# Boost_Converter.net
KiCad netlist of a schematic drawn in Altium Designer
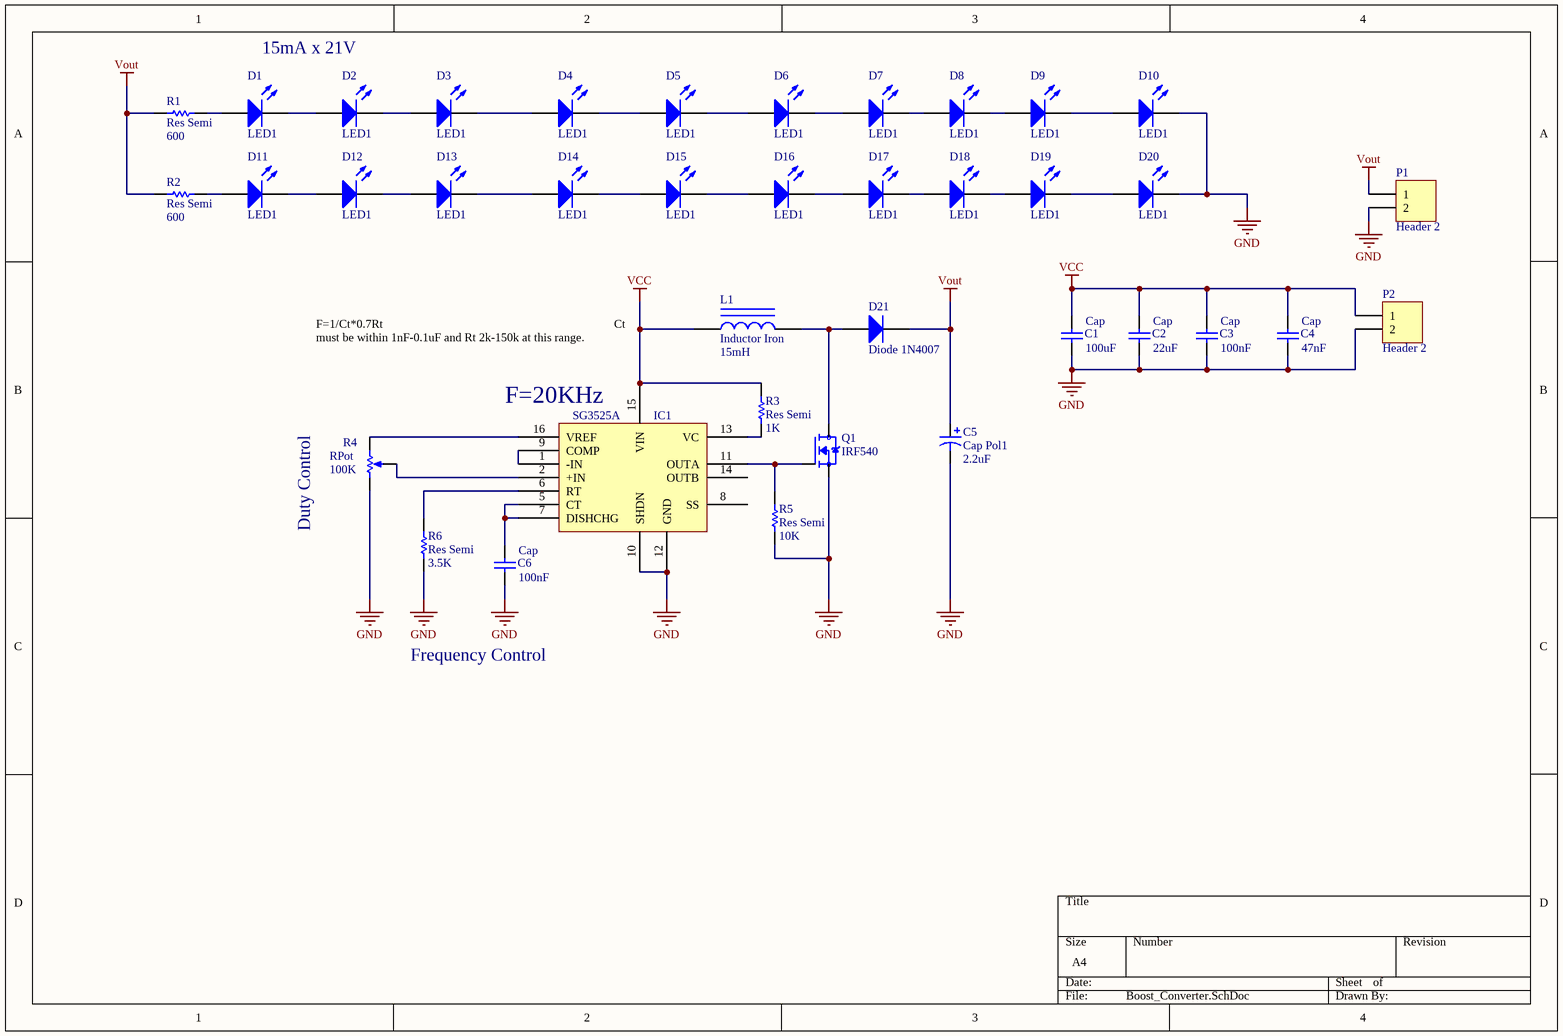
[diagram p0: Boost_Converter.SchDoc]

(export (version "E")
  (design (tool "Eeschema 10.0.6"))
  (components
    (comp (ref "C1")
      (value "Cap")
      (footprint "RAD-0.3")
      (description "Capacitor")
      (fields (field (name "ALTIUM_VALUE") "100uF") (field (name "PUBLISHER") "Altium Limited"))
      (libsource (lib "Miscellaneous Devices") (part "Cap"))
    )
    (comp (ref "C2")
      (value "Cap")
      (footprint "RAD-0.3")
      (description "Capacitor")
      (fields (field (name "ALTIUM_VALUE") "22uF") (field (name "PUBLISHER") "Altium Limited"))
      (libsource (lib "Miscellaneous Devices") (part "Cap"))
    )
    (comp (ref "C3")
      (value "Cap")
      (footprint "RAD-0.3")
      (description "Capacitor")
      (fields (field (name "ALTIUM_VALUE") "100nF") (field (name "PUBLISHER") "Altium Limited"))
      (libsource (lib "Miscellaneous Devices") (part "Cap"))
    )
    (comp (ref "C4")
      (value "Cap")
      (footprint "RAD-0.3")
      (description "Capacitor")
      (fields (field (name "ALTIUM_VALUE") "47nF") (field (name "PUBLISHER") "Altium Limited"))
      (libsource (lib "Miscellaneous Devices") (part "Cap"))
    )
    (comp (ref "C5")
      (value "Cap Pol1")
      (footprint "RB7.6-15")
      (description "Polarized Capacitor (Radial)")
      (fields (field (name "ALTIUM_VALUE") "2.2uF") (field (name "PUBLISHER") "Altium Limited"))
      (libsource (lib "Miscellaneous Devices") (part "Cap Pol1"))
    )
    (comp (ref "C6")
      (value "Cap")
      (footprint "RAD-0.3")
      (description "Capacitor")
      (fields (field (name "ALTIUM_VALUE") "100nF") (field (name "PUBLISHER") "Altium Limited"))
      (libsource (lib "Miscellaneous Devices") (part "Cap"))
    )
    (comp (ref "D1")
      (value "LED1")
      (footprint "LED-1")
      (description "Typical RED GaAs LED")
      (fields (field (name "PUBLISHER") "Altium Limited"))
      (libsource (lib "Miscellaneous Devices") (part "LED1"))
    )
    (comp (ref "D2")
      (value "LED1")
      (footprint "LED-1")
      (description "Typical RED GaAs LED")
      (fields (field (name "PUBLISHER") "Altium Limited"))
      (libsource (lib "Miscellaneous Devices") (part "LED1"))
    )
    (comp (ref "D3")
      (value "LED1")
      (footprint "LED-1")
      (description "Typical RED GaAs LED")
      (fields (field (name "PUBLISHER") "Altium Limited"))
      (libsource (lib "Miscellaneous Devices") (part "LED1"))
    )
    (comp (ref "D4")
      (value "LED1")
      (footprint "LED-1")
      (description "Typical RED GaAs LED")
      (fields (field (name "PUBLISHER") "Altium Limited"))
      (libsource (lib "Miscellaneous Devices") (part "LED1"))
    )
    (comp (ref "D5")
      (value "LED1")
      (footprint "LED-1")
      (description "Typical RED GaAs LED")
      (fields (field (name "PUBLISHER") "Altium Limited"))
      (libsource (lib "Miscellaneous Devices") (part "LED1"))
    )
    (comp (ref "D6")
      (value "LED1")
      (footprint "LED-1")
      (description "Typical RED GaAs LED")
      (fields (field (name "PUBLISHER") "Altium Limited"))
      (libsource (lib "Miscellaneous Devices") (part "LED1"))
    )
    (comp (ref "D7")
      (value "LED1")
      (footprint "LED-1")
      (description "Typical RED GaAs LED")
      (fields (field (name "PUBLISHER") "Altium Limited"))
      (libsource (lib "Miscellaneous Devices") (part "LED1"))
    )
    (comp (ref "D8")
      (value "LED1")
      (footprint "LED-1")
      (description "Typical RED GaAs LED")
      (fields (field (name "PUBLISHER") "Altium Limited"))
      (libsource (lib "Miscellaneous Devices") (part "LED1"))
    )
    (comp (ref "D9")
      (value "LED1")
      (footprint "LED-1")
      (description "Typical RED GaAs LED")
      (fields (field (name "PUBLISHER") "Altium Limited"))
      (libsource (lib "Miscellaneous Devices") (part "LED1"))
    )
    (comp (ref "D10")
      (value "LED1")
      (footprint "LED-1")
      (description "Typical RED GaAs LED")
      (fields (field (name "PUBLISHER") "Altium Limited"))
      (libsource (lib "Miscellaneous Devices") (part "LED1"))
    )
    (comp (ref "D11")
      (value "LED1")
      (footprint "LED-1")
      (description "Typical RED GaAs LED")
      (fields (field (name "PUBLISHER") "Altium Limited"))
      (libsource (lib "Miscellaneous Devices") (part "LED1"))
    )
    (comp (ref "D12")
      (value "LED1")
      (footprint "LED-1")
      (description "Typical RED GaAs LED")
      (fields (field (name "PUBLISHER") "Altium Limited"))
      (libsource (lib "Miscellaneous Devices") (part "LED1"))
    )
    (comp (ref "D13")
      (value "LED1")
      (footprint "LED-1")
      (description "Typical RED GaAs LED")
      (fields (field (name "PUBLISHER") "Altium Limited"))
      (libsource (lib "Miscellaneous Devices") (part "LED1"))
    )
    (comp (ref "D14")
      (value "LED1")
      (footprint "LED-1")
      (description "Typical RED GaAs LED")
      (fields (field (name "PUBLISHER") "Altium Limited"))
      (libsource (lib "Miscellaneous Devices") (part "LED1"))
    )
    (comp (ref "D15")
      (value "LED1")
      (footprint "LED-1")
      (description "Typical RED GaAs LED")
      (fields (field (name "PUBLISHER") "Altium Limited"))
      (libsource (lib "Miscellaneous Devices") (part "LED1"))
    )
    (comp (ref "D16")
      (value "LED1")
      (footprint "LED-1")
      (description "Typical RED GaAs LED")
      (fields (field (name "PUBLISHER") "Altium Limited"))
      (libsource (lib "Miscellaneous Devices") (part "LED1"))
    )
    (comp (ref "D17")
      (value "LED1")
      (footprint "LED-1")
      (description "Typical RED GaAs LED")
      (fields (field (name "PUBLISHER") "Altium Limited"))
      (libsource (lib "Miscellaneous Devices") (part "LED1"))
    )
    (comp (ref "D18")
      (value "LED1")
      (footprint "LED-1")
      (description "Typical RED GaAs LED")
      (fields (field (name "PUBLISHER") "Altium Limited"))
      (libsource (lib "Miscellaneous Devices") (part "LED1"))
    )
    (comp (ref "D19")
      (value "LED1")
      (footprint "LED-1")
      (description "Typical RED GaAs LED")
      (fields (field (name "PUBLISHER") "Altium Limited"))
      (libsource (lib "Miscellaneous Devices") (part "LED1"))
    )
    (comp (ref "D20")
      (value "LED1")
      (footprint "LED-1")
      (description "Typical RED GaAs LED")
      (fields (field (name "PUBLISHER") "Altium Limited"))
      (libsource (lib "Miscellaneous Devices") (part "LED1"))
    )
    (comp (ref "D21")
      (value "Diode 1N4007")
      (footprint "DO-41")
      (description "1 Amp General Purpose Rectifier")
      (fields (field (name "PUBLISHER") "Altium Limited"))
      (libsource (lib "Miscellaneous Devices") (part "Diode 1N4007"))
    )
    (comp (ref "IC1")
      (value "SG3525A")
      (footprint "SG3525A")
      (description "PWM GENERATOR IC")
      (libsource (lib "Boost_Shematic_Lib") (part "SG3525A"))
    )
    (comp (ref "L1")
      (value "Inductor Iron")
      (footprint "AXIAL-0.9")
      (description "Magnetic-Core Inductor")
      (fields (field (name "ALTIUM_VALUE") "15mH") (field (name "PUBLISHER") "Altium Limited"))
      (libsource (lib "Miscellaneous Devices") (part "Inductor Iron"))
    )
    (comp (ref "P1")
      (value "Header 2")
      (footprint "HDR1X2")
      (description "Header, 2-Pin")
      (fields (field (name "PUBLISHER") "Altium Limited"))
      (libsource (lib "Miscellaneous Connectors") (part "Header 2"))
    )
    (comp (ref "P2")
      (value "Header 2")
      (footprint "HDR1X2")
      (description "Header, 2-Pin")
      (fields (field (name "PUBLISHER") "Altium Limited"))
      (libsource (lib "Miscellaneous Connectors") (part "Header 2"))
    )
    (comp (ref "Q1")
      (value "IRF540")
      (footprint "TO254P1052X465X1989-3")
      (description "N-Channel 100V 22A _Tc_ 85W _Tc_ Through Hole TO-220AB")
      (fields (field (name "MF") "Vishay"))
      (libsource (lib "IRF540_mosfet") (part "IRF540"))
    )
    (comp (ref "R1")
      (value "Res Semi")
      (footprint "AXIAL-0.5")
      (description "Semiconductor Resistor")
      (fields (field (name "ALTIUM_VALUE") "600") (field (name "PUBLISHER") "Altium Limited"))
      (libsource (lib "Miscellaneous Devices") (part "Res Semi"))
    )
    (comp (ref "R2")
      (value "Res Semi")
      (footprint "AXIAL-0.5")
      (description "Semiconductor Resistor")
      (fields (field (name "ALTIUM_VALUE") "600") (field (name "PUBLISHER") "Altium Limited"))
      (libsource (lib "Miscellaneous Devices") (part "Res Semi"))
    )
    (comp (ref "R3")
      (value "Res Semi")
      (footprint "AXIAL-0.5")
      (description "Semiconductor Resistor")
      (fields (field (name "ALTIUM_VALUE") "1K") (field (name "PUBLISHER") "Altium Limited"))
      (libsource (lib "Miscellaneous Devices") (part "Res Semi"))
    )
    (comp (ref "R4")
      (value "RPot")
      (footprint "VR5")
      (description "Potentiometer")
      (fields (field (name "ALTIUM_VALUE") "100K") (field (name "PUBLISHER") "Altium Limited"))
      (libsource (lib "Miscellaneous Devices") (part "RPot"))
    )
    (comp (ref "R5")
      (value "Res Semi")
      (footprint "AXIAL-0.5")
      (description "Semiconductor Resistor")
      (fields (field (name "ALTIUM_VALUE") "10K") (field (name "PUBLISHER") "Altium Limited"))
      (libsource (lib "Miscellaneous Devices") (part "Res Semi"))
    )
    (comp (ref "R6")
      (value "Res Semi")
      (footprint "AXIAL-0.5")
      (description "Semiconductor Resistor")
      (fields (field (name "ALTIUM_VALUE") "3.5K") (field (name "PUBLISHER") "Altium Limited"))
      (libsource (lib "Miscellaneous Devices") (part "Res Semi"))
    )
  )
  (nets
    (net (code "1") (name "GND") (class "Default")
      (node (ref "C1") (pin "1") (pinfunction "1_1") (pintype "passive"))
      (node (ref "C2") (pin "1") (pinfunction "1_1") (pintype "passive"))
      (node (ref "C3") (pin "1") (pinfunction "1_1") (pintype "passive"))
      (node (ref "C4") (pin "1") (pinfunction "1_1") (pintype "passive"))
      (node (ref "C5") (pin "2") (pinfunction "2_2") (pintype "passive"))
      (node (ref "C6") (pin "1") (pinfunction "1_1") (pintype "passive"))
      (node (ref "D10") (pin "2") (pinfunction "K_2") (pintype "passive"))
      (node (ref "D20") (pin "2") (pinfunction "K_2") (pintype "passive"))
      (node (ref "IC1") (pin "10") (pinfunction "SHDN_10") (pintype "passive"))
      (node (ref "IC1") (pin "12") (pinfunction "GND_12") (pintype "passive"))
      (node (ref "P1") (pin "2") (pinfunction "2_2") (pintype "passive"))
      (node (ref "P2") (pin "2") (pinfunction "2_2") (pintype "passive"))
      (node (ref "Q1") (pin "3") (pinfunction "S_3") (pintype "passive"))
      (node (ref "R4") (pin "1") (pinfunction "TOP_1") (pintype "passive"))
      (node (ref "R5") (pin "1") (pinfunction "1_1") (pintype "passive"))
      (node (ref "R6") (pin "1") (pinfunction "1_1") (pintype "passive"))
    )
    (net (code "2") (name "Net-(D1-A)") (class "Default")
      (node (ref "D1") (pin "1") (pinfunction "A_1") (pintype "passive"))
      (node (ref "R1") (pin "1") (pinfunction "1_1") (pintype "passive"))
    )
    (net (code "3") (name "Net-(D1-K)") (class "Default")
      (node (ref "D1") (pin "2") (pinfunction "K_2") (pintype "passive"))
      (node (ref "D2") (pin "1") (pinfunction "A_1") (pintype "passive"))
    )
    (net (code "4") (name "Net-(D2-K)") (class "Default")
      (node (ref "D2") (pin "2") (pinfunction "K_2") (pintype "passive"))
      (node (ref "D3") (pin "1") (pinfunction "A_1") (pintype "passive"))
    )
    (net (code "5") (name "Net-(D3-K)") (class "Default")
      (node (ref "D3") (pin "2") (pinfunction "K_2") (pintype "passive"))
      (node (ref "D4") (pin "1") (pinfunction "A_1") (pintype "passive"))
    )
    (net (code "6") (name "Net-(D4-K)") (class "Default")
      (node (ref "D4") (pin "2") (pinfunction "K_2") (pintype "passive"))
      (node (ref "D5") (pin "1") (pinfunction "A_1") (pintype "passive"))
    )
    (net (code "7") (name "Net-(D5-K)") (class "Default")
      (node (ref "D5") (pin "2") (pinfunction "K_2") (pintype "passive"))
      (node (ref "D6") (pin "1") (pinfunction "A_1") (pintype "passive"))
    )
    (net (code "8") (name "Net-(D6-K)") (class "Default")
      (node (ref "D6") (pin "2") (pinfunction "K_2") (pintype "passive"))
      (node (ref "D7") (pin "1") (pinfunction "A_1") (pintype "passive"))
    )
    (net (code "9") (name "Net-(D7-K)") (class "Default")
      (node (ref "D7") (pin "2") (pinfunction "K_2") (pintype "passive"))
      (node (ref "D8") (pin "1") (pinfunction "A_1") (pintype "passive"))
    )
    (net (code "10") (name "Net-(D8-K)") (class "Default")
      (node (ref "D8") (pin "2") (pinfunction "K_2") (pintype "passive"))
      (node (ref "D9") (pin "1") (pinfunction "A_1") (pintype "passive"))
    )
    (net (code "11") (name "Net-(D10-A)") (class "Default")
      (node (ref "D10") (pin "1") (pinfunction "A_1") (pintype "passive"))
      (node (ref "D9") (pin "2") (pinfunction "K_2") (pintype "passive"))
    )
    (net (code "12") (name "Net-(D11-A)") (class "Default")
      (node (ref "D11") (pin "1") (pinfunction "A_1") (pintype "passive"))
      (node (ref "R2") (pin "1") (pinfunction "1_1") (pintype "passive"))
    )
    (net (code "13") (name "Net-(D11-K)") (class "Default")
      (node (ref "D11") (pin "2") (pinfunction "K_2") (pintype "passive"))
      (node (ref "D12") (pin "1") (pinfunction "A_1") (pintype "passive"))
    )
    (net (code "14") (name "Net-(D12-K)") (class "Default")
      (node (ref "D12") (pin "2") (pinfunction "K_2") (pintype "passive"))
      (node (ref "D13") (pin "1") (pinfunction "A_1") (pintype "passive"))
    )
    (net (code "15") (name "Net-(D13-K)") (class "Default")
      (node (ref "D13") (pin "2") (pinfunction "K_2") (pintype "passive"))
      (node (ref "D14") (pin "1") (pinfunction "A_1") (pintype "passive"))
    )
    (net (code "16") (name "Net-(D14-K)") (class "Default")
      (node (ref "D14") (pin "2") (pinfunction "K_2") (pintype "passive"))
      (node (ref "D15") (pin "1") (pinfunction "A_1") (pintype "passive"))
    )
    (net (code "17") (name "Net-(D15-K)") (class "Default")
      (node (ref "D15") (pin "2") (pinfunction "K_2") (pintype "passive"))
      (node (ref "D16") (pin "1") (pinfunction "A_1") (pintype "passive"))
    )
    (net (code "18") (name "Net-(D16-K)") (class "Default")
      (node (ref "D16") (pin "2") (pinfunction "K_2") (pintype "passive"))
      (node (ref "D17") (pin "1") (pinfunction "A_1") (pintype "passive"))
    )
    (net (code "19") (name "Net-(D17-K)") (class "Default")
      (node (ref "D17") (pin "2") (pinfunction "K_2") (pintype "passive"))
      (node (ref "D18") (pin "1") (pinfunction "A_1") (pintype "passive"))
    )
    (net (code "20") (name "Net-(D18-K)") (class "Default")
      (node (ref "D18") (pin "2") (pinfunction "K_2") (pintype "passive"))
      (node (ref "D19") (pin "1") (pinfunction "A_1") (pintype "passive"))
    )
    (net (code "21") (name "Net-(D19-K)") (class "Default")
      (node (ref "D19") (pin "2") (pinfunction "K_2") (pintype "passive"))
      (node (ref "D20") (pin "1") (pinfunction "A_1") (pintype "passive"))
    )
    (net (code "22") (name "Net-(D21-A)") (class "Default")
      (node (ref "D21") (pin "1") (pinfunction "A_1") (pintype "passive"))
      (node (ref "L1") (pin "2") (pinfunction "2_2") (pintype "passive"))
      (node (ref "Q1") (pin "2") (pinfunction "D_2") (pintype "passive"))
    )
    (net (code "23") (name "Net-(IC1-+IN)") (class "Default")
      (node (ref "IC1") (pin "2") (pinfunction "+IN_2") (pintype "passive"))
      (node (ref "R4") (pin "3") (pinfunction "TAP_3") (pintype "passive"))
    )
    (net (code "24") (name "Net-(IC1--IN)") (class "Default")
      (node (ref "IC1") (pin "1") (pinfunction "-IN_1") (pintype "passive"))
      (node (ref "IC1") (pin "9") (pinfunction "COMP_9") (pintype "passive"))
    )
    (net (code "25") (name "Net-(IC1-CT)") (class "Default")
      (node (ref "C6") (pin "2") (pinfunction "2_2") (pintype "passive"))
      (node (ref "IC1") (pin "5") (pinfunction "CT_5") (pintype "passive"))
      (node (ref "IC1") (pin "7") (pinfunction "DISHCHG_7") (pintype "passive"))
    )
    (net (code "26") (name "Net-(IC1-OUTA)") (class "Default")
      (node (ref "IC1") (pin "11") (pinfunction "OUTA_11") (pintype "passive"))
      (node (ref "Q1") (pin "1") (pinfunction "G_1") (pintype "passive"))
      (node (ref "R5") (pin "2") (pinfunction "2_2") (pintype "passive"))
    )
    (net (code "27") (name "Net-(IC1-RT)") (class "Default")
      (node (ref "IC1") (pin "6") (pinfunction "RT_6") (pintype "passive"))
      (node (ref "R6") (pin "2") (pinfunction "2_2") (pintype "passive"))
    )
    (net (code "28") (name "Net-(IC1-VC)") (class "Default")
      (node (ref "IC1") (pin "13") (pinfunction "VC_13") (pintype "passive"))
      (node (ref "R3") (pin "1") (pinfunction "1_1") (pintype "passive"))
    )
    (net (code "29") (name "Net-(IC1-VREF)") (class "Default")
      (node (ref "IC1") (pin "16") (pinfunction "VREF_16") (pintype "passive"))
      (node (ref "R4") (pin "2") (pinfunction "BOT_2") (pintype "passive"))
    )
    (net (code "30") (name "VCC") (class "Default")
      (node (ref "C1") (pin "2") (pinfunction "2_2") (pintype "passive"))
      (node (ref "C2") (pin "2") (pinfunction "2_2") (pintype "passive"))
      (node (ref "C3") (pin "2") (pinfunction "2_2") (pintype "passive"))
      (node (ref "C4") (pin "2") (pinfunction "2_2") (pintype "passive"))
      (node (ref "IC1") (pin "15") (pinfunction "VIN_15") (pintype "passive"))
      (node (ref "L1") (pin "1") (pinfunction "1_1") (pintype "passive"))
      (node (ref "P2") (pin "1") (pinfunction "1_1") (pintype "passive"))
      (node (ref "R3") (pin "2") (pinfunction "2_2") (pintype "passive"))
    )
    (net (code "31") (name "Vout") (class "Default")
      (node (ref "C5") (pin "1") (pinfunction "1_1") (pintype "passive"))
      (node (ref "D21") (pin "2") (pinfunction "K_2") (pintype "passive"))
      (node (ref "P1") (pin "1") (pinfunction "1_1") (pintype "passive"))
      (node (ref "R1") (pin "2") (pinfunction "2_2") (pintype "passive"))
      (node (ref "R2") (pin "2") (pinfunction "2_2") (pintype "passive"))
    )
    (net (code "32") (name "unconnected-(IC1-OUTB-Pad14)") (class "Default")
      (node (ref "IC1") (pin "14") (pinfunction "OUTB_14") (pintype "passive"))
    )
    (net (code "33") (name "unconnected-(IC1-SS-Pad8)") (class "Default")
      (node (ref "IC1") (pin "8") (pinfunction "SS_8") (pintype "passive"))
    )
  )
)
